# 5_-CONNECTORS.net
KiCad netlist of a schematic drawn in Altium Designer
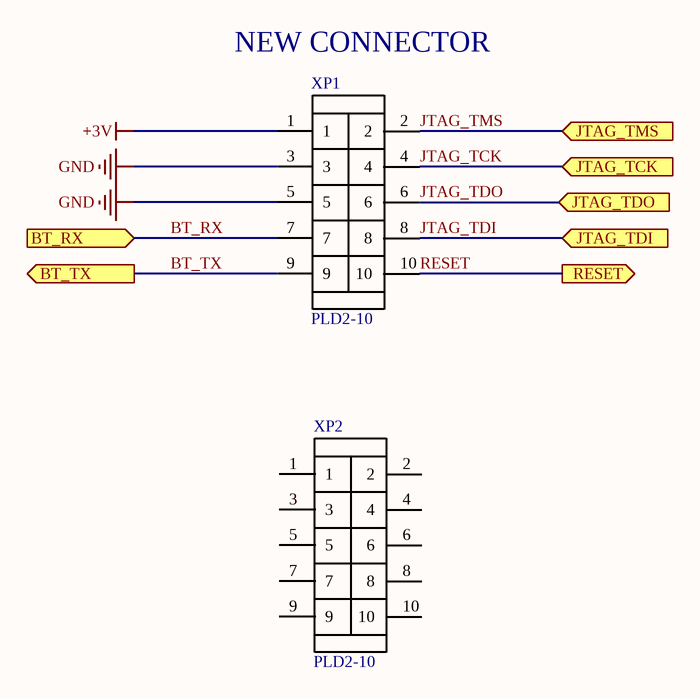
[diagram p0: [5]-CONNECTORS.SchDoc]

(export (version "E")
  (design (tool "Eeschema 10.0.6"))
  (components
    (comp (ref "XP1")
      (value "PLD2-10")
      (footprint "PLD2-10")
      (libsource (lib "gprs_modem_2") (part "PLD2-10"))
    )
    (comp (ref "XP2")
      (value "PLD2-10")
      (footprint "PLD2-10")
      (libsource (lib "gprs_modem_2") (part "PLD2-10"))
    )
  )
  (nets
    (net (code "1") (name "+3V") (class "Default")
      (node (ref "XP1") (pin "1") (pinfunction "1_1") (pintype "passive"))
    )
    (net (code "2") (name "/BT_RX") (class "Default")
      (node (ref "XP1") (pin "7") (pinfunction "7_7") (pintype "passive"))
    )
    (net (code "3") (name "/BT_TX") (class "Default")
      (node (ref "XP1") (pin "9") (pinfunction "9_9") (pintype "passive"))
    )
    (net (code "4") (name "/JTAG_TCK") (class "Default")
      (node (ref "XP1") (pin "4") (pinfunction "4_4") (pintype "passive"))
    )
    (net (code "5") (name "/JTAG_TDI") (class "Default")
      (node (ref "XP1") (pin "8") (pinfunction "8_8") (pintype "passive"))
    )
    (net (code "6") (name "/JTAG_TDO") (class "Default")
      (node (ref "XP1") (pin "6") (pinfunction "6_6") (pintype "passive"))
    )
    (net (code "7") (name "/JTAG_TMS") (class "Default")
      (node (ref "XP1") (pin "2") (pinfunction "2_2") (pintype "passive"))
    )
    (net (code "8") (name "/RESET") (class "Default")
      (node (ref "XP1") (pin "10") (pinfunction "10_10") (pintype "passive"))
    )
    (net (code "9") (name "GND") (class "Default")
      (node (ref "XP1") (pin "3") (pinfunction "3_3") (pintype "passive"))
      (node (ref "XP1") (pin "5") (pinfunction "5_5") (pintype "passive"))
    )
    (net (code "10") (name "unconnected-(XP2-Pad1)") (class "Default")
      (node (ref "XP2") (pin "1") (pinfunction "1_1") (pintype "passive"))
    )
    (net (code "11") (name "unconnected-(XP2-Pad2)") (class "Default")
      (node (ref "XP2") (pin "2") (pinfunction "2_2") (pintype "passive"))
    )
    (net (code "12") (name "unconnected-(XP2-Pad3)") (class "Default")
      (node (ref "XP2") (pin "3") (pinfunction "3_3") (pintype "passive"))
    )
    (net (code "13") (name "unconnected-(XP2-Pad4)") (class "Default")
      (node (ref "XP2") (pin "4") (pinfunction "4_4") (pintype "passive"))
    )
    (net (code "14") (name "unconnected-(XP2-Pad5)") (class "Default")
      (node (ref "XP2") (pin "5") (pinfunction "5_5") (pintype "passive"))
    )
    (net (code "15") (name "unconnected-(XP2-Pad6)") (class "Default")
      (node (ref "XP2") (pin "6") (pinfunction "6_6") (pintype "passive"))
    )
    (net (code "16") (name "unconnected-(XP2-Pad7)") (class "Default")
      (node (ref "XP2") (pin "7") (pinfunction "7_7") (pintype "passive"))
    )
    (net (code "17") (name "unconnected-(XP2-Pad8)") (class "Default")
      (node (ref "XP2") (pin "8") (pinfunction "8_8") (pintype "passive"))
    )
    (net (code "18") (name "unconnected-(XP2-Pad9)") (class "Default")
      (node (ref "XP2") (pin "9") (pinfunction "9_9") (pintype "passive"))
    )
    (net (code "19") (name "unconnected-(XP2-Pad10)") (class "Default")
      (node (ref "XP2") (pin "10") (pinfunction "10_10") (pintype "passive"))
    )
  )
)
